# MCU.net
KiCad netlist of a schematic drawn in Altium Designer
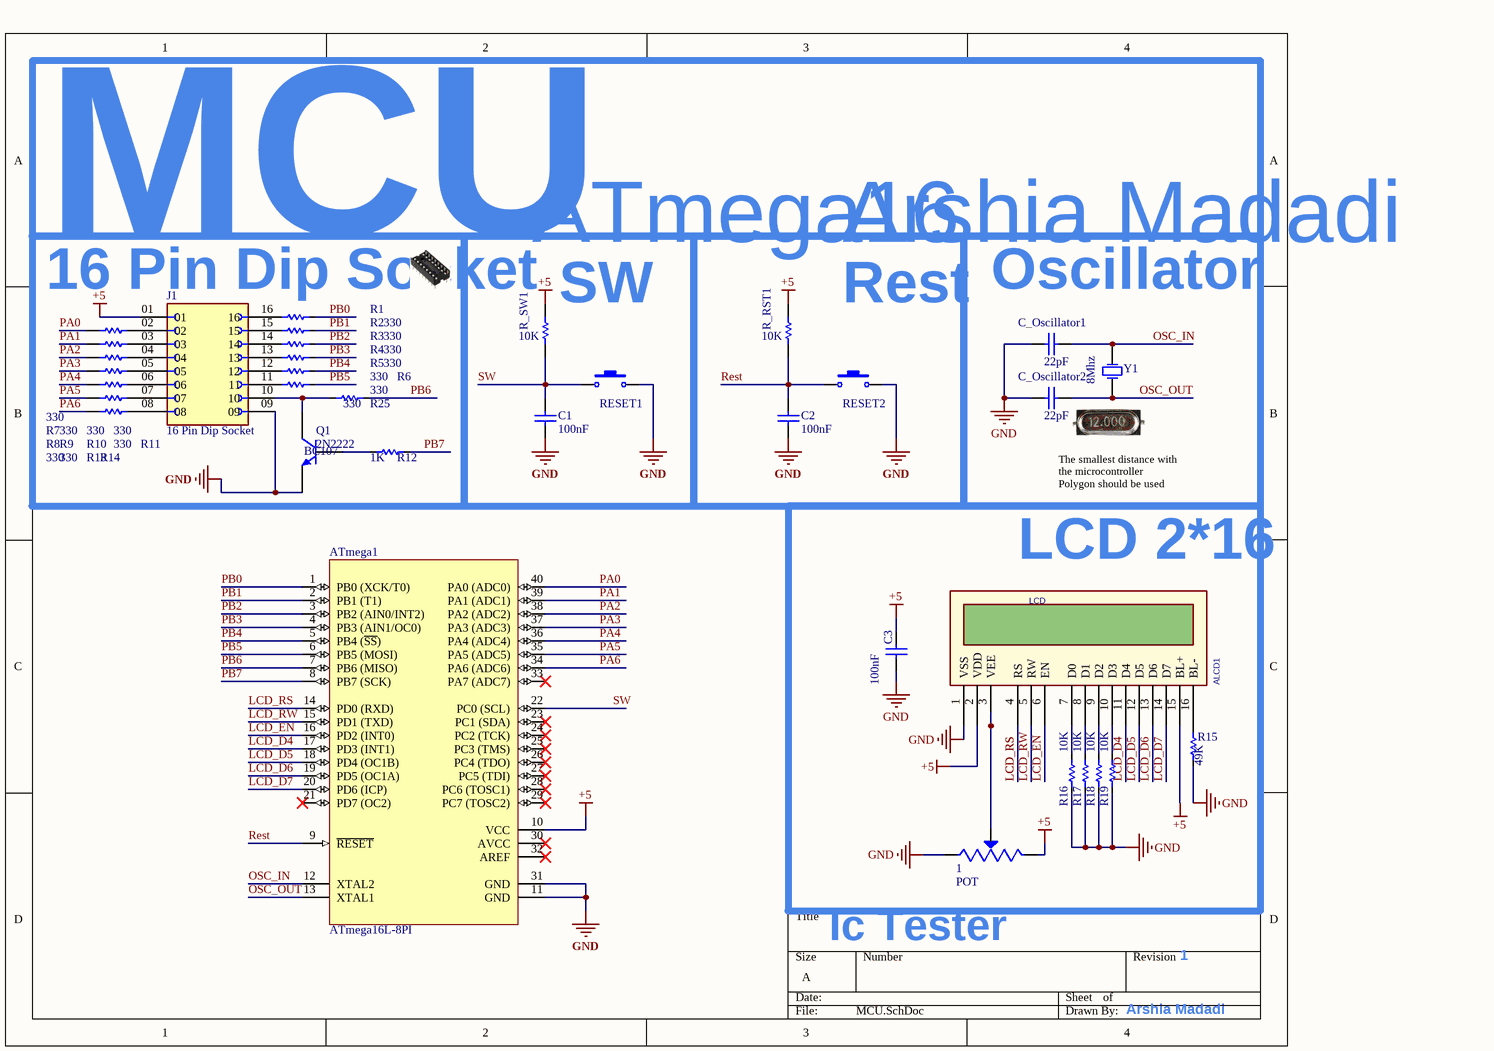
[diagram p0: MCU.SchDoc]

(export (version "E")
  (design (tool "Eeschema 10.0.6"))
  (components
    (comp (ref "1")
      (value "POT")
      (footprint "TRIM_3296W1103LF")
      (description "Trimmer, Potentiometer 10kohm 25turn Thd")
      (fields (field (name "MP") "3296W1103LF") (field (name "MF") "Bourns"))
      (libsource (lib "Multi Turn 3296W-1-103LF") (part "3296W1103LF"))
    )
    (comp (ref "ALCD1")
      (value "LCD")
      (footprint "LCD_2X16 BLUE - 2.5mm")
      (description "Alphanumic LCD")
      (fields (field (name "DESIGNER") "Abbas Basereh"))
      (libsource (lib "Altium") (part "LCD"))
    )
    (comp (ref "ATmega1")
      (value "ATmega16L-8PI")
      (footprint "40P6")
      (description "8-Bit AVR Microcontroller with 16K Bytes of In-System Programmable Flash Memory")
      (fields (field (name "PUBLISHER") "Abbas Basereh"))
      (libsource (lib "Altium") (part "ATmega16L-8PI"))
    )
    (comp (ref "C1")
      (value "100nF")
      (footprint "CAPC4817X12N")
      (description "CAP 1206")
      (fields (field (name "DESIGNER") "Abbas Basereh"))
      (libsource (lib "Altium") (part "CAP SMD 1206"))
    )
    (comp (ref "C2")
      (value "100nF")
      (footprint "CAPC4817X12N")
      (description "CAP 1206")
      (fields (field (name "DESIGNER") "Abbas Basereh"))
      (libsource (lib "Altium") (part "CAP SMD 1206"))
    )
    (comp (ref "C3")
      (value "100nF")
      (footprint "CAPC4817X12N")
      (description "CAP 1206")
      (fields (field (name "DESIGNER") "Abbas Basereh"))
      (libsource (lib "Altium") (part "CAP SMD 1206"))
    )
    (comp (ref "C_Oscillator1")
      (value "22pF")
      (footprint "CAPC4817X12N")
      (description "CAP 1206")
      (fields (field (name "DESIGNER") "Abbas Basereh"))
      (libsource (lib "Altium") (part "CAP SMD 1206"))
    )
    (comp (ref "C_Oscillator2")
      (value "22pF")
      (footprint "CAPC4817X12N")
      (description "CAP 1206")
      (fields (field (name "DESIGNER") "Abbas Basereh"))
      (libsource (lib "Altium") (part "CAP SMD 1206"))
    )
    (comp (ref "J1")
      (value "16 Pin Dip Socket")
      (footprint "AMPHENOL_DILB16P-223TLF")
      (description "DIP Socket, Stamped and Formed")
      (fields (field (name "MF") "Amphenol ICC (FCI)") (field (name "MP") "DILB16P-223TLF"))
      (libsource (lib "DILB16P-223TLF") (part "DILB16P-223TLF"))
    )
    (comp (ref "Q1")
      (value "2N2222")
      (footprint "2N2222")
      (description "NPN Transistor")
      (libsource (lib "Altium") (part "2N2222"))
    )
    (comp (ref "R1")
      (value "330")
      (footprint "1206_Res")
      (description "Resistor")
      (fields (field (name "PUBLISHER") "Altium Limited"))
      (libsource (lib "Sajad_Altium_Library") (part "Res"))
    )
    (comp (ref "R2")
      (value "330")
      (footprint "1206_Res")
      (description "Resistor")
      (fields (field (name "PUBLISHER") "Altium Limited"))
      (libsource (lib "Sajad_Altium_Library") (part "Res"))
    )
    (comp (ref "R3")
      (value "330")
      (footprint "1206_Res")
      (description "Resistor")
      (fields (field (name "PUBLISHER") "Altium Limited"))
      (libsource (lib "Sajad_Altium_Library") (part "Res"))
    )
    (comp (ref "R4")
      (value "330")
      (footprint "1206_Res")
      (description "Resistor")
      (fields (field (name "PUBLISHER") "Altium Limited"))
      (libsource (lib "Sajad_Altium_Library") (part "Res"))
    )
    (comp (ref "R5")
      (value "330")
      (footprint "1206_Res")
      (description "Resistor")
      (fields (field (name "PUBLISHER") "Altium Limited"))
      (libsource (lib "Sajad_Altium_Library") (part "Res"))
    )
    (comp (ref "R6")
      (value "330")
      (footprint "1206_Res")
      (description "Resistor")
      (fields (field (name "PUBLISHER") "Altium Limited"))
      (libsource (lib "Sajad_Altium_Library") (part "Res"))
    )
    (comp (ref "R7")
      (value "330")
      (footprint "RESC4817X04N")
      (description "RES 1206")
      (fields (field (name "DESIGNER") "Abbas Basereh"))
      (libsource (lib "Altium") (part "RES 1206 0.25W"))
    )
    (comp (ref "R8")
      (value "330")
      (footprint "RESC4817X04N")
      (description "RES 1206")
      (fields (field (name "DESIGNER") "Abbas Basereh"))
      (libsource (lib "Altium") (part "RES 1206 0.25W"))
    )
    (comp (ref "R9")
      (value "330")
      (footprint "RESC4817X04N")
      (description "RES 1206")
      (fields (field (name "DESIGNER") "Abbas Basereh"))
      (libsource (lib "Altium") (part "RES 1206 0.25W"))
    )
    (comp (ref "R10")
      (value "330")
      (footprint "RESC4817X04N")
      (description "RES 1206")
      (fields (field (name "DESIGNER") "Abbas Basereh"))
      (libsource (lib "Altium") (part "RES 1206 0.25W"))
    )
    (comp (ref "R11")
      (value "330")
      (footprint "RESC4817X04N")
      (description "RES 1206")
      (fields (field (name "DESIGNER") "Abbas Basereh"))
      (libsource (lib "Altium") (part "RES 1206 0.25W"))
    )
    (comp (ref "R12")
      (value "1K")
      (footprint "1206_Res")
      (description "Resistor")
      (fields (field (name "PUBLISHER") "Altium Limited"))
      (libsource (lib "Sajad_Altium_Library") (part "Res"))
    )
    (comp (ref "R13")
      (value "330")
      (footprint "RESC4817X04N")
      (description "RES 1206")
      (fields (field (name "DESIGNER") "Abbas Basereh"))
      (libsource (lib "Altium") (part "RES 1206 0.25W"))
    )
    (comp (ref "R14")
      (value "330")
      (footprint "RESC4817X04N")
      (description "RES 1206")
      (fields (field (name "DESIGNER") "Abbas Basereh"))
      (libsource (lib "Altium") (part "RES 1206 0.25W"))
    )
    (comp (ref "R15")
      (value "49K")
      (footprint "1206_Res")
      (description "Resistor")
      (fields (field (name "PUBLISHER") "Altium Limited"))
      (libsource (lib "Sajad_Altium_Library") (part "Res"))
    )
    (comp (ref "R16")
      (value "10K")
      (footprint "1206_Res")
      (description "Resistor")
      (fields (field (name "PUBLISHER") "Altium Limited"))
      (libsource (lib "Sajad_Altium_Library") (part "Res"))
    )
    (comp (ref "R17")
      (value "10K")
      (footprint "1206_Res")
      (description "Resistor")
      (fields (field (name "PUBLISHER") "Altium Limited"))
      (libsource (lib "Sajad_Altium_Library") (part "Res"))
    )
    (comp (ref "R18")
      (value "10K")
      (footprint "1206_Res")
      (description "Resistor")
      (fields (field (name "PUBLISHER") "Altium Limited"))
      (libsource (lib "Sajad_Altium_Library") (part "Res"))
    )
    (comp (ref "R19")
      (value "10K")
      (footprint "1206_Res")
      (description "Resistor")
      (fields (field (name "PUBLISHER") "Altium Limited"))
      (libsource (lib "Sajad_Altium_Library") (part "Res"))
    )
    (comp (ref "R25")
      (value "330")
      (footprint "1206_Res")
      (description "Resistor")
      (fields (field (name "PUBLISHER") "Altium Limited"))
      (libsource (lib "Sajad_Altium_Library") (part "Res"))
    )
    (comp (ref "RESET1")
      (value "Switch PB")
      (footprint "Switch - Push to On")
      (description "Push Button Switch")
      (libsource (lib "Altium") (part "Switch PB"))
    )
    (comp (ref "RESET2")
      (value "Switch PB")
      (footprint "Switch - Push to On")
      (description "Push Button Switch")
      (libsource (lib "Altium") (part "Switch PB"))
    )
    (comp (ref "R_RST1")
      (value "10K")
      (footprint "RESC4817X04N")
      (description "RES 1206")
      (fields (field (name "DESIGNER") "Abbas Basereh"))
      (libsource (lib "Altium") (part "RES 1206 0.25W"))
    )
    (comp (ref "R_SW1")
      (value "10K")
      (footprint "RESC4817X04N")
      (description "RES 1206")
      (fields (field (name "DESIGNER") "Abbas Basereh"))
      (libsource (lib "Altium") (part "RES 1206 0.25W"))
    )
    (comp (ref "Y1")
      (value "8Mhz")
      (footprint "Crystal")
      (description "Crystal Oscillator")
      (fields (field (name "PUBLISHER") "Altium Limited"))
      (libsource (lib "Sajad_Altium_Library") (part "XTAL"))
    )
  )
  (nets
    (net (code "1") (name "+5") (class "Default")
      (node (ref "1") (pin "3") (pinfunction "CW_3") (pintype "passive"))
      (node (ref "ALCD1") (pin "15") (pinfunction "BL+_15") (pintype "passive"))
      (node (ref "ALCD1") (pin "2") (pinfunction "VDD_2") (pintype "passive"))
      (node (ref "ATmega1") (pin "10") (pinfunction "VCC_10") (pintype "power_in"))
      (node (ref "C3") (pin "2") (pinfunction "2_2") (pintype "passive"))
      (node (ref "J1") (pin "01") (pinfunction "01_01") (pintype "passive"))
      (node (ref "R_RST1") (pin "2") (pinfunction "2_2") (pintype "passive"))
      (node (ref "R_SW1") (pin "2") (pinfunction "2_2") (pintype "passive"))
    )
    (net (code "2") (name "/LCD_D4") (class "Default")
      (node (ref "ALCD1") (pin "11") (pinfunction "D4_11") (pintype "passive"))
      (node (ref "ATmega1") (pin "17") (pinfunction "PD3_(INT1)_17") (pintype "bidirectional"))
    )
    (net (code "3") (name "/LCD_D5") (class "Default")
      (node (ref "ALCD1") (pin "12") (pinfunction "D5_12") (pintype "passive"))
      (node (ref "ATmega1") (pin "18") (pinfunction "PD4_(OC1B)_18") (pintype "bidirectional"))
    )
    (net (code "4") (name "/LCD_D6") (class "Default")
      (node (ref "ALCD1") (pin "13") (pinfunction "D6_13") (pintype "passive"))
      (node (ref "ATmega1") (pin "19") (pinfunction "PD5_(OC1A)_19") (pintype "bidirectional"))
    )
    (net (code "5") (name "/LCD_D7") (class "Default")
      (node (ref "ALCD1") (pin "14") (pinfunction "D7_14") (pintype "passive"))
      (node (ref "ATmega1") (pin "20") (pinfunction "PD6_(ICP)_20") (pintype "bidirectional"))
    )
    (net (code "6") (name "/LCD_EN") (class "Default")
      (node (ref "ALCD1") (pin "6") (pinfunction "EN_6") (pintype "passive"))
      (node (ref "ATmega1") (pin "16") (pinfunction "PD2_(INT0)_16") (pintype "bidirectional"))
    )
    (net (code "7") (name "/LCD_RS") (class "Default")
      (node (ref "ALCD1") (pin "4") (pinfunction "RS_4") (pintype "passive"))
      (node (ref "ATmega1") (pin "14") (pinfunction "PD0_(RXD)_14") (pintype "bidirectional"))
    )
    (net (code "8") (name "/LCD_RW") (class "Default")
      (node (ref "ALCD1") (pin "5") (pinfunction "RW_5") (pintype "passive"))
      (node (ref "ATmega1") (pin "15") (pinfunction "PD1_(TXD)_15") (pintype "bidirectional"))
    )
    (net (code "9") (name "/OSC_IN") (class "Default")
      (node (ref "ATmega1") (pin "12") (pinfunction "XTAL2_12") (pintype "passive"))
      (node (ref "C_Oscillator1") (pin "2") (pinfunction "2_2") (pintype "passive"))
      (node (ref "Y1") (pin "2") (pinfunction "OSC2_2") (pintype "passive"))
    )
    (net (code "10") (name "/OSC_OUT") (class "Default")
      (node (ref "ATmega1") (pin "13") (pinfunction "XTAL1_13") (pintype "passive"))
      (node (ref "C_Oscillator2") (pin "2") (pinfunction "2_2") (pintype "passive"))
      (node (ref "Y1") (pin "1") (pinfunction "OSC1_1") (pintype "passive"))
    )
    (net (code "11") (name "/PA0") (class "Default")
      (node (ref "ATmega1") (pin "40") (pinfunction "PA0_(ADC0)_40") (pintype "bidirectional"))
      (node (ref "R10") (pin "2") (pinfunction "2_2") (pintype "passive"))
    )
    (net (code "12") (name "/PA1") (class "Default")
      (node (ref "ATmega1") (pin "39") (pinfunction "PA1_(ADC1)_39") (pintype "bidirectional"))
      (node (ref "R9") (pin "2") (pinfunction "2_2") (pintype "passive"))
    )
    (net (code "13") (name "/PA2") (class "Default")
      (node (ref "ATmega1") (pin "38") (pinfunction "PA2_(ADC2)_38") (pintype "bidirectional"))
      (node (ref "R14") (pin "2") (pinfunction "2_2") (pintype "passive"))
    )
    (net (code "14") (name "/PA3") (class "Default")
      (node (ref "ATmega1") (pin "37") (pinfunction "PA3_(ADC3)_37") (pintype "bidirectional"))
      (node (ref "R13") (pin "2") (pinfunction "2_2") (pintype "passive"))
    )
    (net (code "15") (name "/PA4") (class "Default")
      (node (ref "ATmega1") (pin "36") (pinfunction "PA4_(ADC4)_36") (pintype "bidirectional"))
      (node (ref "R11") (pin "2") (pinfunction "2_2") (pintype "passive"))
    )
    (net (code "16") (name "/PA5") (class "Default")
      (node (ref "ATmega1") (pin "35") (pinfunction "PA5_(ADC5)_35") (pintype "bidirectional"))
      (node (ref "R8") (pin "2") (pinfunction "2_2") (pintype "passive"))
    )
    (net (code "17") (name "/PA6") (class "Default")
      (node (ref "ATmega1") (pin "34") (pinfunction "PA6_(ADC6)_34") (pintype "bidirectional"))
      (node (ref "R7") (pin "2") (pinfunction "2_2") (pintype "passive"))
    )
    (net (code "18") (name "/PB0") (class "Default")
      (node (ref "ATmega1") (pin "1") (pinfunction "PB0_(XCK/T0)_1") (pintype "bidirectional"))
      (node (ref "R1") (pin "1") (pinfunction "1_1") (pintype "passive"))
    )
    (net (code "19") (name "/PB1") (class "Default")
      (node (ref "ATmega1") (pin "2") (pinfunction "PB1_(T1)_2") (pintype "bidirectional"))
      (node (ref "R2") (pin "1") (pinfunction "1_1") (pintype "passive"))
    )
    (net (code "20") (name "/PB2") (class "Default")
      (node (ref "ATmega1") (pin "3") (pinfunction "PB2_(AIN0/INT2)_3") (pintype "bidirectional"))
      (node (ref "R3") (pin "1") (pinfunction "1_1") (pintype "passive"))
    )
    (net (code "21") (name "/PB3") (class "Default")
      (node (ref "ATmega1") (pin "4") (pinfunction "PB3_(AIN1/OC0)_4") (pintype "bidirectional"))
      (node (ref "R4") (pin "1") (pinfunction "1_1") (pintype "passive"))
    )
    (net (code "22") (name "/PB4") (class "Default")
      (node (ref "ATmega1") (pin "5") (pinfunction "PB4_(~{SS})_5") (pintype "bidirectional"))
      (node (ref "R5") (pin "1") (pinfunction "1_1") (pintype "passive"))
    )
    (net (code "23") (name "/PB5") (class "Default")
      (node (ref "ATmega1") (pin "6") (pinfunction "PB5_(MOSI)_6") (pintype "bidirectional"))
      (node (ref "R6") (pin "1") (pinfunction "1_1") (pintype "passive"))
    )
    (net (code "24") (name "/PB6") (class "Default")
      (node (ref "ATmega1") (pin "7") (pinfunction "PB6_(MISO)_7") (pintype "bidirectional"))
      (node (ref "R25") (pin "1") (pinfunction "1_1") (pintype "passive"))
    )
    (net (code "25") (name "/PB7") (class "Default")
      (node (ref "ATmega1") (pin "8") (pinfunction "PB7_(SCK)_8") (pintype "bidirectional"))
      (node (ref "R12") (pin "1") (pinfunction "1_1") (pintype "passive"))
    )
    (net (code "26") (name "/Rest") (class "Default")
      (node (ref "ATmega1") (pin "9") (pinfunction "~{RESET}_9") (pintype "input"))
      (node (ref "C2") (pin "2") (pinfunction "2_2") (pintype "passive"))
      (node (ref "RESET2") (pin "1") (pinfunction "1_1") (pintype "passive"))
      (node (ref "R_RST1") (pin "1") (pinfunction "1_1") (pintype "passive"))
    )
    (net (code "27") (name "/SW") (class "Default")
      (node (ref "ATmega1") (pin "22") (pinfunction "PC0_(SCL)_22") (pintype "bidirectional"))
      (node (ref "C1") (pin "2") (pinfunction "2_2") (pintype "passive"))
      (node (ref "RESET1") (pin "1") (pinfunction "1_1") (pintype "passive"))
      (node (ref "R_SW1") (pin "1") (pinfunction "1_1") (pintype "passive"))
    )
    (net (code "28") (name "GND") (class "Default")
      (node (ref "1") (pin "1") (pinfunction "CCW_1") (pintype "passive"))
      (node (ref "ALCD1") (pin "1") (pinfunction "VSS_1") (pintype "passive"))
      (node (ref "ATmega1") (pin "11") (pinfunction "GND_11") (pintype "power_in"))
      (node (ref "ATmega1") (pin "31") (pinfunction "GND_31") (pintype "power_in"))
      (node (ref "C1") (pin "1") (pinfunction "1_1") (pintype "passive"))
      (node (ref "C2") (pin "1") (pinfunction "1_1") (pintype "passive"))
      (node (ref "C3") (pin "1") (pinfunction "1_1") (pintype "passive"))
      (node (ref "C_Oscillator1") (pin "1") (pinfunction "1_1") (pintype "passive"))
      (node (ref "C_Oscillator2") (pin "1") (pinfunction "1_1") (pintype "passive"))
      (node (ref "J1") (pin "09") (pinfunction "09_09") (pintype "passive"))
      (node (ref "Q1") (pin "1") (pinfunction "E_1") (pintype "passive"))
      (node (ref "R15") (pin "2") (pinfunction "2_2") (pintype "passive"))
      (node (ref "R16") (pin "1") (pinfunction "1_1") (pintype "passive"))
      (node (ref "R17") (pin "1") (pinfunction "1_1") (pintype "passive"))
      (node (ref "R18") (pin "1") (pinfunction "1_1") (pintype "passive"))
      (node (ref "R19") (pin "1") (pinfunction "1_1") (pintype "passive"))
      (node (ref "RESET1") (pin "2") (pinfunction "2_2") (pintype "passive"))
      (node (ref "RESET2") (pin "2") (pinfunction "2_2") (pintype "passive"))
    )
    (net (code "29") (name "Net-(1-WIPER)") (class "Default")
      (node (ref "1") (pin "2") (pinfunction "WIPER_2") (pintype "passive"))
      (node (ref "ALCD1") (pin "3") (pinfunction "VEE_3") (pintype "passive"))
    )
    (net (code "30") (name "Net-(ALCD1-BL-)") (class "Default")
      (node (ref "ALCD1") (pin "16") (pinfunction "BL-_16") (pintype "passive"))
      (node (ref "R15") (pin "1") (pinfunction "1_1") (pintype "passive"))
    )
    (net (code "31") (name "Net-(ALCD1-D0)") (class "Default")
      (node (ref "ALCD1") (pin "7") (pinfunction "D0_7") (pintype "passive"))
      (node (ref "R16") (pin "2") (pinfunction "2_2") (pintype "passive"))
    )
    (net (code "32") (name "Net-(ALCD1-D1)") (class "Default")
      (node (ref "ALCD1") (pin "8") (pinfunction "D1_8") (pintype "passive"))
      (node (ref "R17") (pin "2") (pinfunction "2_2") (pintype "passive"))
    )
    (net (code "33") (name "Net-(ALCD1-D2)") (class "Default")
      (node (ref "ALCD1") (pin "9") (pinfunction "D2_9") (pintype "passive"))
      (node (ref "R18") (pin "2") (pinfunction "2_2") (pintype "passive"))
    )
    (net (code "34") (name "Net-(ALCD1-D3)") (class "Default")
      (node (ref "ALCD1") (pin "10") (pinfunction "D3_10") (pintype "passive"))
      (node (ref "R19") (pin "2") (pinfunction "2_2") (pintype "passive"))
    )
    (net (code "35") (name "Net-(J1-Pad02)") (class "Default")
      (node (ref "J1") (pin "02") (pinfunction "02_02") (pintype "passive"))
      (node (ref "R10") (pin "1") (pinfunction "1_1") (pintype "passive"))
    )
    (net (code "36") (name "Net-(J1-Pad03)") (class "Default")
      (node (ref "J1") (pin "03") (pinfunction "03_03") (pintype "passive"))
      (node (ref "R9") (pin "1") (pinfunction "1_1") (pintype "passive"))
    )
    (net (code "37") (name "Net-(J1-Pad04)") (class "Default")
      (node (ref "J1") (pin "04") (pinfunction "04_04") (pintype "passive"))
      (node (ref "R14") (pin "1") (pinfunction "1_1") (pintype "passive"))
    )
    (net (code "38") (name "Net-(J1-Pad05)") (class "Default")
      (node (ref "J1") (pin "05") (pinfunction "05_05") (pintype "passive"))
      (node (ref "R13") (pin "1") (pinfunction "1_1") (pintype "passive"))
    )
    (net (code "39") (name "Net-(J1-Pad06)") (class "Default")
      (node (ref "J1") (pin "06") (pinfunction "06_06") (pintype "passive"))
      (node (ref "R11") (pin "1") (pinfunction "1_1") (pintype "passive"))
    )
    (net (code "40") (name "Net-(J1-Pad07)") (class "Default")
      (node (ref "J1") (pin "07") (pinfunction "07_07") (pintype "passive"))
      (node (ref "R8") (pin "1") (pinfunction "1_1") (pintype "passive"))
    )
    (net (code "41") (name "Net-(J1-Pad08)") (class "Default")
      (node (ref "J1") (pin "08") (pinfunction "08_08") (pintype "passive"))
      (node (ref "R7") (pin "1") (pinfunction "1_1") (pintype "passive"))
    )
    (net (code "42") (name "Net-(J1-Pad11)") (class "Default")
      (node (ref "J1") (pin "11") (pinfunction "11_11") (pintype "passive"))
      (node (ref "R6") (pin "2") (pinfunction "2_2") (pintype "passive"))
    )
    (net (code "43") (name "Net-(J1-Pad12)") (class "Default")
      (node (ref "J1") (pin "12") (pinfunction "12_12") (pintype "passive"))
      (node (ref "R5") (pin "2") (pinfunction "2_2") (pintype "passive"))
    )
    (net (code "44") (name "Net-(J1-Pad13)") (class "Default")
      (node (ref "J1") (pin "13") (pinfunction "13_13") (pintype "passive"))
      (node (ref "R4") (pin "2") (pinfunction "2_2") (pintype "passive"))
    )
    (net (code "45") (name "Net-(J1-Pad14)") (class "Default")
      (node (ref "J1") (pin "14") (pinfunction "14_14") (pintype "passive"))
      (node (ref "R3") (pin "2") (pinfunction "2_2") (pintype "passive"))
    )
    (net (code "46") (name "Net-(J1-Pad15)") (class "Default")
      (node (ref "J1") (pin "15") (pinfunction "15_15") (pintype "passive"))
      (node (ref "R2") (pin "2") (pinfunction "2_2") (pintype "passive"))
    )
    (net (code "47") (name "Net-(J1-Pad16)") (class "Default")
      (node (ref "J1") (pin "16") (pinfunction "16_16") (pintype "passive"))
      (node (ref "R1") (pin "2") (pinfunction "2_2") (pintype "passive"))
    )
    (net (code "48") (name "Net-(Q1-B)") (class "Default")
      (node (ref "Q1") (pin "2") (pinfunction "B_2") (pintype "passive"))
      (node (ref "R12") (pin "2") (pinfunction "2_2") (pintype "passive"))
    )
    (net (code "49") (name "Net-(Q1-C)") (class "Default")
      (node (ref "J1") (pin "10") (pinfunction "10_10") (pintype "passive"))
      (node (ref "Q1") (pin "3") (pinfunction "C_3") (pintype "passive"))
      (node (ref "R25") (pin "2") (pinfunction "2_2") (pintype "passive"))
    )
    (net (code "50") (name "unconnected-(ATmega1-AREF-Pad32)") (class "Default")
      (node (ref "ATmega1") (pin "32") (pinfunction "AREF_32") (pintype "passive+no_connect"))
    )
    (net (code "51") (name "unconnected-(ATmega1-AVCC-Pad30)") (class "Default")
      (node (ref "ATmega1") (pin "30") (pinfunction "AVCC_30") (pintype "power_in+no_connect"))
    )
    (net (code "52") (name "unconnected-(ATmega1-PA7_(ADC7)-Pad33)") (class "Default")
      (node (ref "ATmega1") (pin "33") (pinfunction "PA7_(ADC7)_33") (pintype "bidirectional+no_connect"))
    )
    (net (code "53") (name "unconnected-(ATmega1-PC1_(SDA)-Pad23)") (class "Default")
      (node (ref "ATmega1") (pin "23") (pinfunction "PC1_(SDA)_23") (pintype "bidirectional+no_connect"))
    )
    (net (code "54") (name "unconnected-(ATmega1-PC2_(TCK)-Pad24)") (class "Default")
      (node (ref "ATmega1") (pin "24") (pinfunction "PC2_(TCK)_24") (pintype "bidirectional+no_connect"))
    )
    (net (code "55") (name "unconnected-(ATmega1-PC3_(TMS)-Pad25)") (class "Default")
      (node (ref "ATmega1") (pin "25") (pinfunction "PC3_(TMS)_25") (pintype "bidirectional+no_connect"))
    )
    (net (code "56") (name "unconnected-(ATmega1-PC4_(TDO)-Pad26)") (class "Default")
      (node (ref "ATmega1") (pin "26") (pinfunction "PC4_(TDO)_26") (pintype "bidirectional+no_connect"))
    )
    (net (code "57") (name "unconnected-(ATmega1-PC5_(TDI)-Pad27)") (class "Default")
      (node (ref "ATmega1") (pin "27") (pinfunction "PC5_(TDI)_27") (pintype "bidirectional+no_connect"))
    )
    (net (code "58") (name "unconnected-(ATmega1-PC6_(TOSC1)-Pad28)") (class "Default")
      (node (ref "ATmega1") (pin "28") (pinfunction "PC6_(TOSC1)_28") (pintype "bidirectional+no_connect"))
    )
    (net (code "59") (name "unconnected-(ATmega1-PC7_(TOSC2)-Pad29)") (class "Default")
      (node (ref "ATmega1") (pin "29") (pinfunction "PC7_(TOSC2)_29") (pintype "bidirectional+no_connect"))
    )
    (net (code "60") (name "unconnected-(ATmega1-PD7_(OC2)-Pad21)") (class "Default")
      (node (ref "ATmega1") (pin "21") (pinfunction "PD7_(OC2)_21") (pintype "bidirectional+no_connect"))
    )
  )
)
